# ST_LINK_V2.net
KiCad netlist of a schematic drawn in Altium Designer
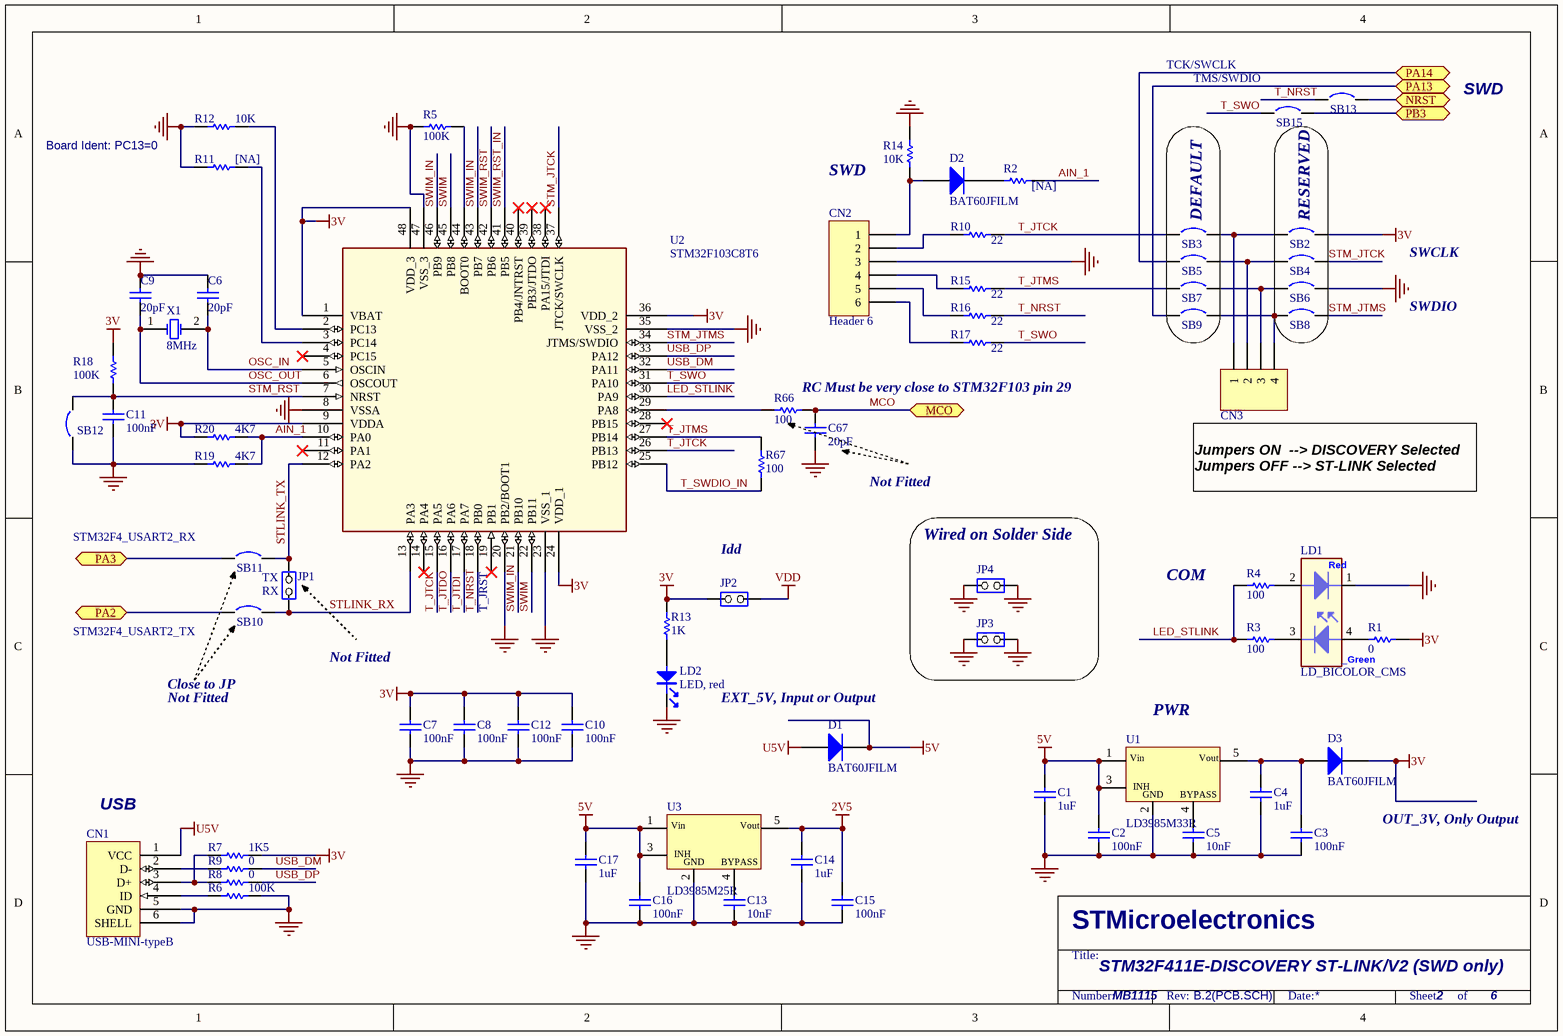
[diagram p0: ST_LINK_V2.SCHDOC]

(export (version "E")
  (design (tool "Eeschema 10.0.6"))
  (components
    (comp (ref "C1")
      (value "1uF")
      (footprint "0603C")
      (description "Capacitor,1uF,16V,X5R,10%,0603,YAGEO")
      (libsource (lib "MCD_TOOLS") (part "Cap_1uF_X5R_10%_0603"))
    )
    (comp (ref "C2")
      (value "100nF")
      (footprint "0402C")
      (description "Capacitor,100nF,16V,X7R,10%,0402,YAGEO")
      (libsource (lib "MCD_TOOLS") (part "Cap_100nF_X7R_10%_0402"))
    )
    (comp (ref "C3")
      (value "100nF")
      (footprint "0402C")
      (description "Capacitor,100nF,16V,X7R,10%,0402,YAGEO")
      (libsource (lib "MCD_TOOLS") (part "Cap_100nF_X7R_10%_0402"))
    )
    (comp (ref "C4")
      (value "1uF")
      (footprint "0603C")
      (description "Capacitor,1uF,16V,X5R,10%,0603,YAGEO")
      (libsource (lib "MCD_TOOLS") (part "Cap_1uF_X5R_10%_0603"))
    )
    (comp (ref "C5")
      (value "10nF")
      (footprint "0603C")
      (description "Capacitor,10nF,50V,X7R,10%,0603,YAGEO")
      (libsource (lib "MCD_TOOLS") (part "Cap_10nF_X7R_10%_0603"))
    )
    (comp (ref "C6")
      (value "20pF")
      (footprint "0402C")
      (description "Capacitor,20pF,50V,NPO,5%,0402,YAGEO")
      (libsource (lib "MCD_TOOLS") (part "Cap_20pF_NPO_5%_0402"))
    )
    (comp (ref "C7")
      (value "100nF")
      (footprint "0402C")
      (description "Capacitor,100nF,16V,X7R,10%,0402,YAGEO")
      (libsource (lib "MCD_TOOLS") (part "Cap_100nF_X7R_10%_0402"))
    )
    (comp (ref "C8")
      (value "100nF")
      (footprint "0402C")
      (description "Capacitor,100nF,16V,X7R,10%,0402,YAGEO")
      (libsource (lib "MCD_TOOLS") (part "Cap_100nF_X7R_10%_0402"))
    )
    (comp (ref "C9")
      (value "20pF")
      (footprint "0402C")
      (description "Capacitor,20pF,50V,NPO,5%,0402,YAGEO")
      (libsource (lib "MCD_TOOLS") (part "Cap_20pF_NPO_5%_0402"))
    )
    (comp (ref "C10")
      (value "100nF")
      (footprint "0402C")
      (description "Capacitor,100nF,16V,X7R,10%,0402,YAGEO")
      (libsource (lib "MCD_TOOLS") (part "Cap_100nF_X7R_10%_0402"))
    )
    (comp (ref "C11")
      (value "100nF")
      (footprint "0402C")
      (description "Capacitor,100nF,16V,X7R,10%,0402,YAGEO")
      (libsource (lib "MCD_TOOLS") (part "Cap_100nF_X7R_10%_0402"))
    )
    (comp (ref "C12")
      (value "100nF")
      (footprint "0402C")
      (description "Capacitor,100nF,16V,X7R,10%,0402,YAGEO")
      (libsource (lib "MCD_TOOLS") (part "Cap_100nF_X7R_10%_0402"))
    )
    (comp (ref "C13")
      (value "10nF")
      (footprint "0603C")
      (description "Capacitor,10nF,50V,X7R,10%,0603,YAGEO")
      (libsource (lib "MCD_TOOLS") (part "Cap_10nF_X7R_10%_0603"))
    )
    (comp (ref "C14")
      (value "1uF")
      (footprint "0603C")
      (description "Capacitor,1uF,16V,X5R,10%,0603,YAGEO")
      (libsource (lib "MCD_TOOLS") (part "Cap_1uF_X5R_10%_0603"))
    )
    (comp (ref "C15")
      (value "100nF")
      (footprint "0402C")
      (description "Capacitor,100nF,16V,X7R,10%,0402,YAGEO")
      (libsource (lib "MCD_TOOLS") (part "Cap_100nF_X7R_10%_0402"))
    )
    (comp (ref "C16")
      (value "100nF")
      (footprint "0402C")
      (description "Capacitor,100nF,16V,X7R,10%,0402,YAGEO")
      (libsource (lib "MCD_TOOLS") (part "Cap_100nF_X7R_10%_0402"))
    )
    (comp (ref "C17")
      (value "1uF")
      (footprint "0603C")
      (description "Capacitor,1uF,16V,X5R,10%,0603,YAGEO")
      (libsource (lib "MCD_TOOLS") (part "Cap_1uF_X5R_10%_0603"))
    )
    (comp (ref "C67")
      (value "20pF")
      (footprint "0402C")
      (description "Capacitor,20pF,50V,NPO,5%,0402,YAGEO")
      (libsource (lib "MCD_TOOLS") (part "Cap_20pF_NPO_5%_0402"))
    )
    (comp (ref "CN1")
      (value "USB-MINI-typeB")
      (footprint "STM-SMEE:USB-MINI-B-SMD")
      (description "USB,MINI-USB-5P/F, 5075BMR-05-M")
      (libsource (lib "MCD_TOOLS") (part "USB-MINI-typeB connector"))
    )
    (comp (ref "CN2")
      (value "Header 6")
      (footprint "HDR1X6")
      (description "Header, 6-Pin")
      (fields (field (name "PUBLISHER") "Altium Limited"))
      (libsource (lib "Miscellaneous Connectors") (part "Header 6"))
    )
    (comp (ref "CN3")
      (value "Header 4")
      (footprint "Header 4")
      (description "Header, 4-Pin")
      (fields (field (name "PUBLISHER") "Altium Limited"))
      (libsource (lib "MB963_1") (part "Header 4"))
    )
    (comp (ref "D1")
      (value "BAT60JFILM")
      (footprint "STM-SMEE:SOD323/A")
      (libsource (lib "MCD_TOOLS") (part "BAT60JFILM"))
    )
    (comp (ref "D2")
      (value "BAT60JFILM")
      (footprint "STM-SMEE:SOD323/A")
      (libsource (lib "MCD_TOOLS") (part "BAT60JFILM"))
    )
    (comp (ref "D3")
      (value "BAT60JFILM")
      (footprint "STM-SMEE:SOD323/A")
      (libsource (lib "MCD_TOOLS") (part "BAT60JFILM"))
    )
    (comp (ref "JP1") (value "JP2") (footprint "SIP2/2.54") (libsource (lib "MCD_TOOLS") (part "JP2")))
    (comp (ref "JP2") (value "~") (footprint "SIP2/2.54") (libsource (lib "*") (part "JP2")))
    (comp (ref "JP3") (value "~") (footprint "SIP2/2.54") (libsource (lib "*") (part "JP2")))
    (comp (ref "JP4") (value "~") (footprint "SIP2/2.54") (libsource (lib "*") (part "JP2")))
    (comp (ref "LD1")
      (value "LD_BICOLOR_CMS")
      (footprint "STM-SMEE:HSMF-A201")
      (description "Bicolor Led")
      (libsource (lib "MCD_TOOLS") (part "LD_BICOLOR_CMS"))
    )
    (comp (ref "LD2")
      (value "LED, red")
      (footprint "0603D")
      (description "LED,red,0603,19-213-R6C-AP1Q2B/3T,everlight")
      (libsource (lib "MCD_TOOLS") (part "LED_red"))
    )
    (comp (ref "R1")
      (value "0")
      (footprint "STM-SMEE:0402R")
      (description "Resistor,0,0402")
      (libsource (lib "MCD_TOOLS") (part "Res_0_0402"))
    )
    (comp (ref "R2")
      (value "[NA]")
      (footprint "STM-SMEE:0402R")
      (description "Resistor,[NA],0402")
      (libsource (lib "MCD_TOOLS") (part "Res_NA_0402"))
    )
    (comp (ref "R3")
      (value "100")
      (footprint "0402R")
      (description "Resistor")
      (fields (field (name "PUBLISHER") "Altium Limited"))
      (libsource (lib "MB915_1") (part "res1"))
    )
    (comp (ref "R4")
      (value "100")
      (footprint "0402R")
      (description "Resistor")
      (fields (field (name "PUBLISHER") "Altium Limited"))
      (libsource (lib "MB915_1") (part "res1"))
    )
    (comp (ref "R5")
      (value "100K")
      (footprint "0402R")
      (description "Resistor")
      (fields (field (name "PUBLISHER") "Altium Limited"))
      (libsource (lib "MB915_1") (part "res1"))
    )
    (comp (ref "R6")
      (value "100K")
      (footprint "0402R")
      (description "Resistor")
      (fields (field (name "PUBLISHER") "Altium Limited"))
      (libsource (lib "MB915_1") (part "res1"))
    )
    (comp (ref "R7")
      (value "1K5")
      (footprint "0402R")
      (description "Resistor")
      (fields (field (name "PUBLISHER") "Altium Limited"))
      (libsource (lib "MB915_1") (part "res1"))
    )
    (comp (ref "R8")
      (value "0")
      (footprint "STM-SMEE:0402R")
      (description "Resistor,0,0402")
      (libsource (lib "MCD_TOOLS") (part "Res_0_0402"))
    )
    (comp (ref "R9")
      (value "0")
      (footprint "STM-SMEE:0402R")
      (description "Resistor,0,0402")
      (libsource (lib "MCD_TOOLS") (part "Res_0_0402"))
    )
    (comp (ref "R10")
      (value "22")
      (footprint "0402R")
      (description "Resistor")
      (fields (field (name "PUBLISHER") "Altium Limited"))
      (libsource (lib "MB915_1") (part "res1"))
    )
    (comp (ref "R11")
      (value "[NA]")
      (footprint "STM-SMEE:0402R")
      (description "Resistor,[NA],0402")
      (libsource (lib "MCD_TOOLS") (part "Res_NA_0402"))
    )
    (comp (ref "R12")
      (value "10K")
      (footprint "0402R")
      (description "Resistor")
      (fields (field (name "PUBLISHER") "Altium Limited"))
      (libsource (lib "MB915_1") (part "res1"))
    )
    (comp (ref "R13")
      (value "1K")
      (footprint "0402R")
      (description "Resistor")
      (fields (field (name "PUBLISHER") "Altium Limited"))
      (libsource (lib "MB915_1") (part "res1"))
    )
    (comp (ref "R14")
      (value "10K")
      (footprint "0402R")
      (description "Resistor")
      (fields (field (name "PUBLISHER") "Altium Limited"))
      (libsource (lib "MB915_1") (part "res1"))
    )
    (comp (ref "R15")
      (value "22")
      (footprint "0402R")
      (description "Resistor")
      (fields (field (name "PUBLISHER") "Altium Limited"))
      (libsource (lib "MB915_1") (part "res1"))
    )
    (comp (ref "R16")
      (value "22")
      (footprint "0402R")
      (description "Resistor")
      (fields (field (name "PUBLISHER") "Altium Limited"))
      (libsource (lib "MB915_1") (part "res1"))
    )
    (comp (ref "R17")
      (value "22")
      (footprint "0402R")
      (description "Resistor")
      (fields (field (name "PUBLISHER") "Altium Limited"))
      (libsource (lib "MB915_1") (part "res1"))
    )
    (comp (ref "R18")
      (value "100K")
      (footprint "0402R")
      (description "Resistor")
      (fields (field (name "PUBLISHER") "Altium Limited"))
      (libsource (lib "MB915_1") (part "res1"))
    )
    (comp (ref "R19")
      (value "4K7")
      (footprint "0402R")
      (description "Resistor")
      (fields (field (name "PUBLISHER") "Altium Limited"))
      (libsource (lib "MB915_1") (part "res1"))
    )
    (comp (ref "R20")
      (value "4K7")
      (footprint "0402R")
      (description "Resistor")
      (fields (field (name "PUBLISHER") "Altium Limited"))
      (libsource (lib "MB915_1") (part "res1"))
    )
    (comp (ref "R66")
      (value "100")
      (footprint "0402R")
      (description "Resistor")
      (fields (field (name "PUBLISHER") "Altium Limited"))
      (libsource (lib "MB915_1") (part "res1"))
    )
    (comp (ref "R67")
      (value "100")
      (footprint "0402R")
      (description "Resistor")
      (fields (field (name "PUBLISHER") "Altium Limited"))
      (libsource (lib "MB915_1") (part "res1"))
    )
    (comp (ref "SB2")
      (value "Circuit Breaker")
      (footprint "JP2_SMD")
      (libsource (lib "MCD_TOOLS") (part "Circuit Breaker"))
    )
    (comp (ref "SB3")
      (value "Circuit Breaker")
      (footprint "JP2_SMD")
      (libsource (lib "MCD_TOOLS") (part "Circuit Breaker"))
    )
    (comp (ref "SB4")
      (value "Circuit Breaker")
      (footprint "JP2_SMD")
      (libsource (lib "MCD_TOOLS") (part "Circuit Breaker"))
    )
    (comp (ref "SB5")
      (value "Circuit Breaker")
      (footprint "JP2_SMD")
      (libsource (lib "MCD_TOOLS") (part "Circuit Breaker"))
    )
    (comp (ref "SB6")
      (value "Circuit Breaker")
      (footprint "JP2_SMD")
      (libsource (lib "MCD_TOOLS") (part "Circuit Breaker"))
    )
    (comp (ref "SB7")
      (value "Circuit Breaker")
      (footprint "JP2_SMD")
      (libsource (lib "MCD_TOOLS") (part "Circuit Breaker"))
    )
    (comp (ref "SB8")
      (value "Circuit Breaker")
      (footprint "JP2_SMD")
      (libsource (lib "MCD_TOOLS") (part "Circuit Breaker"))
    )
    (comp (ref "SB9")
      (value "Circuit Breaker")
      (footprint "JP2_SMD")
      (libsource (lib "MCD_TOOLS") (part "Circuit Breaker"))
    )
    (comp (ref "SB10")
      (value "Circuit Breaker")
      (footprint "JP2_SMD")
      (libsource (lib "MCD_TOOLS") (part "Circuit Breaker"))
    )
    (comp (ref "SB11")
      (value "Circuit Breaker")
      (footprint "JP2_SMD")
      (libsource (lib "MCD_TOOLS") (part "Circuit Breaker"))
    )
    (comp (ref "SB12")
      (value "Circuit Breaker")
      (footprint "JP2_SMD")
      (libsource (lib "MCD_TOOLS") (part "Circuit Breaker"))
    )
    (comp (ref "SB13")
      (value "Circuit Breaker")
      (footprint "JP2_SMD")
      (libsource (lib "MCD_TOOLS") (part "Circuit Breaker"))
    )
    (comp (ref "SB15")
      (value "Circuit Breaker")
      (footprint "JP2_SMD")
      (libsource (lib "MCD_TOOLS") (part "Circuit Breaker"))
    )
    (comp (ref "U1")
      (value "LD3985M33R")
      (footprint "STM-SMEE:SOT-23-5L")
      (description "Ultra low drop-low noise BiCMOS voltage, regulators low ESR capacitors compatible")
      (libsource (lib "MCD_TOOLS") (part "LD3985M33R"))
    )
    (comp (ref "U2")
      (value "STM32F103C8T6")
      (footprint "STM-SMEE:QFP48 7X7")
      (description "Medium-density performance line ARM-based 32-bit MCU with 64KB Flash")
      (libsource (lib "MCD_TOOLS") (part "STM32F103C8T6"))
    )
    (comp (ref "U3")
      (value "LD3985M25R")
      (footprint "STM-SMEE:SOT-23-5L")
      (description "Ultra low drop-low noise BiCMOS voltage, regulators low ESR capacitors compatible")
      (libsource (lib "MCD_TOOLS") (part "LD3985M25R"))
    )
    (comp (ref "X1")
      (value "8MHz")
      (footprint "STM-SMEE:XTAL1")
      (description "Crystal Oscillator,8Mhz,20PF,20PPM,-10-70 degree,DIP,HC-49S")
      (libsource (lib "MCD_TOOLS") (part "XTAL_8MHZ_20PPM"))
    )
  )
  (nets
    (net (code "1") (name "/AIN_1") (class "Default")
      (node (ref "R19") (pin "2") (pinfunction "2_2") (pintype "passive"))
      (node (ref "R2") (pin "2") (pinfunction "2_2") (pintype "passive"))
      (node (ref "R20") (pin "2") (pinfunction "2_2") (pintype "passive"))
      (node (ref "U2") (pin "10") (pinfunction "PA0_10") (pintype "bidirectional"))
    )
    (net (code "2") (name "/LED_STLINK") (class "Default")
      (node (ref "R3") (pin "1") (pinfunction "1_1") (pintype "passive"))
      (node (ref "R4") (pin "1") (pinfunction "1_1") (pintype "passive"))
      (node (ref "U2") (pin "30") (pinfunction "PA9_30") (pintype "bidirectional"))
    )
    (net (code "3") (name "/MCO") (class "Default")
      (node (ref "C67") (pin "1") (pinfunction "1_1") (pintype "passive"))
      (node (ref "R66") (pin "2") (pinfunction "2_2") (pintype "passive"))
    )
    (net (code "4") (name "/NRST") (class "Default")
      (node (ref "SB13") (pin "2") (pinfunction "2_2") (pintype "passive"))
    )
    (net (code "5") (name "/OSC_IN") (class "Default")
      (node (ref "C6") (pin "2") (pinfunction "2_2") (pintype "passive"))
      (node (ref "U2") (pin "5") (pinfunction "OSCIN_5") (pintype "input"))
      (node (ref "X1") (pin "2") (pinfunction "OSC2_2") (pintype "passive"))
    )
    (net (code "6") (name "/OSC_OUT") (class "Default")
      (node (ref "C9") (pin "2") (pinfunction "2_2") (pintype "passive"))
      (node (ref "U2") (pin "6") (pinfunction "OSCOUT_6") (pintype "output"))
      (node (ref "X1") (pin "1") (pinfunction "OSC1_1") (pintype "passive"))
    )
    (net (code "7") (name "/PA2") (class "Default")
      (node (ref "SB10") (pin "1") (pinfunction "1_1") (pintype "passive"))
    )
    (net (code "8") (name "/PA3") (class "Default")
      (node (ref "SB11") (pin "1") (pinfunction "1_1") (pintype "passive"))
    )
    (net (code "9") (name "/PA13") (class "Default")
      (node (ref "SB9") (pin "1") (pinfunction "1_1") (pintype "passive"))
    )
    (net (code "10") (name "/PA14") (class "Default")
      (node (ref "SB5") (pin "1") (pinfunction "1_1") (pintype "passive"))
    )
    (net (code "11") (name "/PB3") (class "Default")
      (node (ref "SB15") (pin "2") (pinfunction "2_2") (pintype "passive"))
    )
    (net (code "12") (name "/STLINK_RX") (class "Default")
      (node (ref "JP1") (pin "1") (pinfunction "COMMON_1") (pintype "passive"))
      (node (ref "SB10") (pin "2") (pinfunction "2_2") (pintype "passive"))
      (node (ref "U2") (pin "13") (pinfunction "PA3_13") (pintype "bidirectional"))
    )
    (net (code "13") (name "/STLINK_TX") (class "Default")
      (node (ref "JP1") (pin "2") (pinfunction "NO_2") (pintype "passive"))
      (node (ref "SB11") (pin "2") (pinfunction "2_2") (pintype "passive"))
      (node (ref "U2") (pin "12") (pinfunction "PA2_12") (pintype "bidirectional"))
    )
    (net (code "14") (name "/STM_JTCK") (class "Default")
      (node (ref "SB4") (pin "2") (pinfunction "2_2") (pintype "passive"))
      (node (ref "U2") (pin "37") (pinfunction "JTCK/SWCLK_37") (pintype "bidirectional"))
    )
    (net (code "15") (name "/STM_JTMS") (class "Default")
      (node (ref "SB8") (pin "2") (pinfunction "2_2") (pintype "passive"))
      (node (ref "U2") (pin "34") (pinfunction "JTMS/SWDIO_34") (pintype "bidirectional"))
    )
    (net (code "16") (name "/STM_RST") (class "Default")
      (node (ref "C11") (pin "2") (pinfunction "2_2") (pintype "passive"))
      (node (ref "R18") (pin "1") (pinfunction "1_1") (pintype "passive"))
      (node (ref "SB12") (pin "2") (pinfunction "2_2") (pintype "passive"))
      (node (ref "U2") (pin "7") (pinfunction "NRST_7") (pintype "input"))
    )
    (net (code "17") (name "/SWIM") (class "Default")
      (node (ref "U2") (pin "22") (pinfunction "PB11_22") (pintype "bidirectional"))
      (node (ref "U2") (pin "45") (pinfunction "PB8_45") (pintype "bidirectional"))
    )
    (net (code "18") (name "/SWIM_IN") (class "Default")
      (node (ref "U2") (pin "21") (pinfunction "PB10_21") (pintype "bidirectional"))
      (node (ref "U2") (pin "43") (pinfunction "PB7_43") (pintype "bidirectional"))
      (node (ref "U2") (pin "46") (pinfunction "PB9_46") (pintype "bidirectional"))
    )
    (net (code "19") (name "/SWIM_RST") (class "Default")
      (node (ref "U2") (pin "42") (pinfunction "PB6_42") (pintype "bidirectional"))
    )
    (net (code "20") (name "/SWIM_RST_IN") (class "Default")
      (node (ref "U2") (pin "41") (pinfunction "PB5_41") (pintype "bidirectional"))
    )
    (net (code "21") (name "/T_JTCK") (class "Default")
      (node (ref "R10") (pin "2") (pinfunction "2_2") (pintype "passive"))
      (node (ref "SB3") (pin "1") (pinfunction "1_1") (pintype "passive"))
      (node (ref "U2") (pin "15") (pinfunction "PA5_15") (pintype "bidirectional"))
      (node (ref "U2") (pin "26") (pinfunction "PB13_26") (pintype "bidirectional"))
    )
    (net (code "22") (name "/T_JTDI") (class "Default")
      (node (ref "U2") (pin "17") (pinfunction "PA7_17") (pintype "bidirectional"))
    )
    (net (code "23") (name "/T_JTDO") (class "Default")
      (node (ref "U2") (pin "16") (pinfunction "PA6_16") (pintype "bidirectional"))
    )
    (net (code "24") (name "/T_JTMS") (class "Default")
      (node (ref "R15") (pin "2") (pinfunction "2_2") (pintype "passive"))
      (node (ref "R67") (pin "2") (pinfunction "2_2") (pintype "passive"))
      (node (ref "SB7") (pin "1") (pinfunction "1_1") (pintype "passive"))
      (node (ref "U2") (pin "27") (pinfunction "PB14_27") (pintype "bidirectional"))
    )
    (net (code "25") (name "/T_NRST") (class "Default")
      (node (ref "R16") (pin "2") (pinfunction "2_2") (pintype "passive"))
      (node (ref "SB13") (pin "1") (pinfunction "1_1") (pintype "passive"))
      (node (ref "U2") (pin "18") (pinfunction "PB0_18") (pintype "bidirectional"))
    )
    (net (code "26") (name "/T_SWDIO_IN") (class "Default")
      (node (ref "R67") (pin "1") (pinfunction "1_1") (pintype "passive"))
      (node (ref "U2") (pin "25") (pinfunction "PB12_25") (pintype "bidirectional"))
    )
    (net (code "27") (name "/T_SWO") (class "Default")
      (node (ref "R17") (pin "2") (pinfunction "2_2") (pintype "passive"))
      (node (ref "SB15") (pin "1") (pinfunction "1_1") (pintype "passive"))
      (node (ref "U2") (pin "31") (pinfunction "PA10_31") (pintype "bidirectional"))
    )
    (net (code "28") (name "/USB_DM") (class "Default")
      (node (ref "R9") (pin "2") (pinfunction "2_2") (pintype "passive"))
      (node (ref "U2") (pin "32") (pinfunction "PA11_32") (pintype "bidirectional"))
    )
    (net (code "29") (name "/USB_DP") (class "Default")
      (node (ref "R8") (pin "2") (pinfunction "2_2") (pintype "passive"))
      (node (ref "U2") (pin "33") (pinfunction "PA12_33") (pintype "bidirectional"))
    )
    (net (code "30") (name "2V5") (class "Default")
      (node (ref "C14") (pin "1") (pinfunction "1_1") (pintype "passive"))
      (node (ref "C15") (pin "2") (pinfunction "2_2") (pintype "passive"))
      (node (ref "U3") (pin "5") (pinfunction "Vout_5") (pintype "passive"))
    )
    (net (code "31") (name "3V") (class "Default")
      (node (ref "C10") (pin "2") (pinfunction "2_2") (pintype "passive"))
      (node (ref "C12") (pin "1") (pinfunction "1_1") (pintype "passive"))
      (node (ref "C7") (pin "2") (pinfunction "2_2") (pintype "passive"))
      (node (ref "C8") (pin "2") (pinfunction "2_2") (pintype "passive"))
      (node (ref "D3") (pin "2") (pinfunction "K_2") (pintype "passive"))
      (node (ref "JP2") (pin "1") (pinfunction "COMMON_1") (pintype "passive"))
      (node (ref "R1") (pin "2") (pinfunction "2_2") (pintype "passive"))
      (node (ref "R13") (pin "2") (pinfunction "2_2") (pintype "passive"))
      (node (ref "R18") (pin "2") (pinfunction "2_2") (pintype "passive"))
      (node (ref "R20") (pin "1") (pinfunction "1_1") (pintype "passive"))
      (node (ref "R7") (pin "2") (pinfunction "2_2") (pintype "passive"))
      (node (ref "SB2") (pin "2") (pinfunction "2_2") (pintype "passive"))
      (node (ref "U2") (pin "1") (pinfunction "VBAT_1") (pintype "power_in"))
      (node (ref "U2") (pin "24") (pinfunction "VDD_1_24") (pintype "power_in"))
      (node (ref "U2") (pin "36") (pinfunction "VDD_2_36") (pintype "power_in"))
      (node (ref "U2") (pin "48") (pinfunction "VDD_3_48") (pintype "power_in"))
      (node (ref "U2") (pin "9") (pinfunction "VDDA_9") (pintype "power_in"))
    )
    (net (code "32") (name "5V") (class "Default")
      (node (ref "C1") (pin "2") (pinfunction "2_2") (pintype "passive"))
      (node (ref "C16") (pin "2") (pinfunction "2_2") (pintype "passive"))
      (node (ref "C17") (pin "2") (pinfunction "2_2") (pintype "passive"))
      (node (ref "C2") (pin "2") (pinfunction "2_2") (pintype "passive"))
      (node (ref "D1") (pin "2") (pinfunction "K_2") (pintype "passive"))
      (node (ref "U1") (pin "1") (pinfunction "Vin_1") (pintype "passive"))
      (node (ref "U1") (pin "3") (pinfunction "CE_3") (pintype "passive"))
      (node (ref "U3") (pin "1") (pinfunction "Vin_1") (pintype "passive"))
      (node (ref "U3") (pin "3") (pinfunction "CE_3") (pintype "passive"))
    )
    (net (code "33") (name "GND") (class "Default")
      (node (ref "C1") (pin "1") (pinfunction "1_1") (pintype "passive"))
      (node (ref "C10") (pin "1") (pinfunction "1_1") (pintype "passive"))
      (node (ref "C11") (pin "1") (pinfunction "1_1") (pintype "passive"))
      (node (ref "C12") (pin "2") (pinfunction "2_2") (pintype "passive"))
      (node (ref "C13") (pin "1") (pinfunction "1_1") (pintype "passive"))
      (node (ref "C14") (pin "2") (pinfunction "2_2") (pintype "passive"))
      (node (ref "C15") (pin "1") (pinfunction "1_1") (pintype "passive"))
      (node (ref "C16") (pin "1") (pinfunction "1_1") (pintype "passive"))
      (node (ref "C17") (pin "1") (pinfunction "1_1") (pintype "passive"))
      (node (ref "C2") (pin "1") (pinfunction "1_1") (pintype "passive"))
      (node (ref "C3") (pin "1") (pinfunction "1_1") (pintype "passive"))
      (node (ref "C4") (pin "2") (pinfunction "2_2") (pintype "passive"))
      (node (ref "C5") (pin "1") (pinfunction "1_1") (pintype "passive"))
      (node (ref "C6") (pin "1") (pinfunction "1_1") (pintype "passive"))
      (node (ref "C67") (pin "2") (pinfunction "2_2") (pintype "passive"))
      (node (ref "C7") (pin "1") (pinfunction "1_1") (pintype "passive"))
      (node (ref "C8") (pin "1") (pinfunction "1_1") (pintype "passive"))
      (node (ref "C9") (pin "1") (pinfunction "1_1") (pintype "passive"))
      (node (ref "CN1") (pin "5") (pinfunction "GND_5") (pintype "passive"))
      (node (ref "CN1") (pin "6") (pinfunction "SHELL_6") (pintype "passive"))
      (node (ref "CN2") (pin "3") (pinfunction "3_3") (pintype "passive"))
      (node (ref "JP3") (pin "1") (pinfunction "COMMON_1") (pintype "passive"))
      (node (ref "JP3") (pin "2") (pinfunction "NO_2") (pintype "passive"))
      (node (ref "JP4") (pin "1") (pinfunction "COMMON_1") (pintype "passive"))
      (node (ref "JP4") (pin "2") (pinfunction "NO_2") (pintype "passive"))
      (node (ref "LD1") (pin "1") (pinfunction "1_1") (pintype "passive"))
      (node (ref "LD2") (pin "2") (pintype "passive"))
      (node (ref "R11") (pin "1") (pinfunction "1_1") (pintype "passive"))
      (node (ref "R12") (pin "1") (pinfunction "1_1") (pintype "passive"))
      (node (ref "R14") (pin "2") (pinfunction "2_2") (pintype "passive"))
      (node (ref "R19") (pin "1") (pinfunction "1_1") (pintype "passive"))
      (node (ref "R5") (pin "1") (pinfunction "1_1") (pintype "passive"))
      (node (ref "R6") (pin "2") (pinfunction "2_2") (pintype "passive"))
      (node (ref "SB12") (pin "1") (pinfunction "1_1") (pintype "passive"))
      (node (ref "SB6") (pin "2") (pinfunction "2_2") (pintype "passive"))
      (node (ref "U1") (pin "2") (pinfunction "GND_2") (pintype "passive"))
      (node (ref "U2") (pin "20") (pinfunction "PB2/BOOT1_20") (pintype "bidirectional"))
      (node (ref "U2") (pin "23") (pinfunction "VSS_1_23") (pintype "power_in"))
      (node (ref "U2") (pin "35") (pinfunction "VSS_2_35") (pintype "power_in"))
      (node (ref "U2") (pin "47") (pinfunction "VSS_3_47") (pintype "power_in"))
      (node (ref "U2") (pin "8") (pinfunction "VSSA_8") (pintype "power_in"))
      (node (ref "U3") (pin "2") (pinfunction "GND_2") (pintype "passive"))
    )
    (net (code "34") (name "Net-(CN1-D+)") (class "Default")
      (node (ref "CN1") (pin "3") (pinfunction "D+_3") (pintype "bidirectional"))
      (node (ref "R7") (pin "1") (pinfunction "1_1") (pintype "passive"))
      (node (ref "R8") (pin "1") (pinfunction "1_1") (pintype "passive"))
    )
    (net (code "35") (name "Net-(CN1-D-)") (class "Default")
      (node (ref "CN1") (pin "2") (pinfunction "D-_2") (pintype "bidirectional"))
      (node (ref "R9") (pin "1") (pinfunction "1_1") (pintype "passive"))
    )
    (net (code "36") (name "Net-(CN1-ID)") (class "Default")
      (node (ref "CN1") (pin "4") (pinfunction "ID_4") (pintype "input"))
      (node (ref "R6") (pin "1") (pinfunction "1_1") (pintype "passive"))
    )
    (net (code "37") (name "Net-(CN2-Pad2)") (class "Default")
      (node (ref "CN2") (pin "2") (pinfunction "2_2") (pintype "passive"))
      (node (ref "R10") (pin "1") (pinfunction "1_1") (pintype "passive"))
    )
    (net (code "38") (name "Net-(CN2-Pad4)") (class "Default")
      (node (ref "CN2") (pin "4") (pinfunction "4_4") (pintype "passive"))
      (node (ref "R15") (pin "1") (pinfunction "1_1") (pintype "passive"))
    )
    (net (code "39") (name "Net-(CN2-Pad5)") (class "Default")
      (node (ref "CN2") (pin "5") (pinfunction "5_5") (pintype "passive"))
      (node (ref "R16") (pin "1") (pinfunction "1_1") (pintype "passive"))
    )
    (net (code "40") (name "Net-(CN2-Pad6)") (class "Default")
      (node (ref "CN2") (pin "6") (pinfunction "6_6") (pintype "passive"))
      (node (ref "R17") (pin "1") (pinfunction "1_1") (pintype "passive"))
    )
    (net (code "41") (name "Net-(CN3-Pad1)") (class "Default")
      (node (ref "CN3") (pin "1") (pinfunction "1_1") (pintype "passive"))
      (node (ref "SB2") (pin "1") (pinfunction "1_1") (pintype "passive"))
      (node (ref "SB3") (pin "2") (pinfunction "2_2") (pintype "passive"))
    )
    (net (code "42") (name "Net-(CN3-Pad2)") (class "Default")
      (node (ref "CN3") (pin "2") (pinfunction "2_2") (pintype "passive"))
      (node (ref "SB4") (pin "1") (pinfunction "1_1") (pintype "passive"))
      (node (ref "SB5") (pin "2") (pinfunction "2_2") (pintype "passive"))
    )
    (net (code "43") (name "Net-(CN3-Pad3)") (class "Default")
      (node (ref "CN3") (pin "3") (pinfunction "3_3") (pintype "passive"))
      (node (ref "SB6") (pin "1") (pinfunction "1_1") (pintype "passive"))
      (node (ref "SB7") (pin "2") (pinfunction "2_2") (pintype "passive"))
    )
    (net (code "44") (name "Net-(CN3-Pad4)") (class "Default")
      (node (ref "CN3") (pin "4") (pinfunction "4_4") (pintype "passive"))
      (node (ref "SB8") (pin "1") (pinfunction "1_1") (pintype "passive"))
      (node (ref "SB9") (pin "2") (pinfunction "2_2") (pintype "passive"))
    )
    (net (code "45") (name "Net-(D2-A)") (class "Default")
      (node (ref "CN2") (pin "1") (pinfunction "1_1") (pintype "passive"))
      (node (ref "D2") (pin "1") (pinfunction "A_1") (pintype "passive"))
      (node (ref "R14") (pin "1") (pinfunction "1_1") (pintype "passive"))
    )
    (net (code "46") (name "Net-(D2-K)") (class "Default")
      (node (ref "D2") (pin "2") (pinfunction "K_2") (pintype "passive"))
      (node (ref "R2") (pin "1") (pinfunction "1_1") (pintype "passive"))
    )
    (net (code "47") (name "Net-(D3-A)") (class "Default")
      (node (ref "C3") (pin "2") (pinfunction "2_2") (pintype "passive"))
      (node (ref "C4") (pin "1") (pinfunction "1_1") (pintype "passive"))
      (node (ref "D3") (pin "1") (pinfunction "A_1") (pintype "passive"))
      (node (ref "U1") (pin "5") (pinfunction "Vout_5") (pintype "passive"))
    )
    (net (code "48") (name "Net-(LD1-Pad2)") (class "Default")
      (node (ref "LD1") (pin "2") (pinfunction "2_2") (pintype "passive"))
      (node (ref "R4") (pin "2") (pinfunction "2_2") (pintype "passive"))
    )
    (net (code "49") (name "Net-(LD1-Pad3)") (class "Default")
      (node (ref "LD1") (pin "3") (pinfunction "3_3") (pintype "passive"))
      (node (ref "R3") (pin "2") (pinfunction "2_2") (pintype "passive"))
    )
    (net (code "50") (name "Net-(LD1-Pad4)") (class "Default")
      (node (ref "LD1") (pin "4") (pinfunction "4_4") (pintype "passive"))
      (node (ref "R1") (pin "1") (pinfunction "1_1") (pintype "passive"))
    )
    (net (code "51") (name "Net-(LD2-Pad1)") (class "Default")
      (node (ref "LD2") (pin "1") (pintype "passive"))
      (node (ref "R13") (pin "1") (pinfunction "1_1") (pintype "passive"))
    )
    (net (code "52") (name "Net-(U1-BYPASS)") (class "Default")
      (node (ref "C5") (pin "2") (pinfunction "2_2") (pintype "passive"))
      (node (ref "U1") (pin "4") (pinfunction "BYPASS_4") (pintype "passive"))
    )
    (net (code "53") (name "Net-(U2-BOOT0)") (class "Default")
      (node (ref "R5") (pin "2") (pinfunction "2_2") (pintype "passive"))
      (node (ref "U2") (pin "44") (pinfunction "BOOT0_44") (pintype "bidirectional"))
    )
    (net (code "54") (name "Net-(U2-PA8)") (class "Default")
      (node (ref "R66") (pin "1") (pinfunction "1_1") (pintype "passive"))
      (node (ref "U2") (pin "29") (pinfunction "PA8_29") (pintype "bidirectional"))
    )
    (net (code "55") (name "Net-(U2-PC13)") (class "Default")
      (node (ref "R12") (pin "2") (pinfunction "2_2") (pintype "passive"))
      (node (ref "U2") (pin "2") (pinfunction "PC13_2") (pintype "bidirectional"))
    )
    (net (code "56") (name "Net-(U2-PC14)") (class "Default")
      (node (ref "R11") (pin "2") (pinfunction "2_2") (pintype "passive"))
      (node (ref "U2") (pin "3") (pinfunction "PC14_3") (pintype "bidirectional"))
    )
    (net (code "57") (name "Net-(U3-BYPASS)") (class "Default")
      (node (ref "C13") (pin "2") (pinfunction "2_2") (pintype "passive"))
      (node (ref "U3") (pin "4") (pinfunction "BYPASS_4") (pintype "passive"))
    )
    (net (code "58") (name "U5V") (class "Default")
      (node (ref "CN1") (pin "1") (pinfunction "VCC_1") (pintype "power_in"))
      (node (ref "D1") (pin "1") (pinfunction "A_1") (pintype "passive"))
    )
    (net (code "59") (name "VDD") (class "Default")
      (node (ref "JP2") (pin "2") (pinfunction "NO_2") (pintype "passive"))
    )
    (net (code "60") (name "unconnected-(U2-PA1-Pad11)") (class "Default")
      (node (ref "U2") (pin "11") (pinfunction "PA1_11") (pintype "bidirectional+no_connect"))
    )
    (net (code "61") (name "unconnected-(U2-PA4-Pad14)") (class "Default")
      (node (ref "U2") (pin "14") (pinfunction "PA4_14") (pintype "bidirectional+no_connect"))
    )
    (net (code "62") (name "unconnected-(U2-PA15{slash}JTDI-Pad38)") (class "Default")
      (node (ref "U2") (pin "38") (pinfunction "PA15/JTDI_38") (pintype "bidirectional+no_connect"))
    )
    (net (code "63") (name "unconnected-(U2-PB1-Pad19)") (class "Default")
      (node (ref "U2") (pin "19") (pinfunction "PB1_19") (pintype "input+no_connect"))
    )
    (net (code "64") (name "unconnected-(U2-PB3{slash}JTDO-Pad39)") (class "Default")
      (node (ref "U2") (pin "39") (pinfunction "PB3/JTDO_39") (pintype "bidirectional+no_connect"))
    )
    (net (code "65") (name "unconnected-(U2-PB4{slash}JNTRST-Pad40)") (class "Default")
      (node (ref "U2") (pin "40") (pinfunction "PB4/JNTRST_40") (pintype "bidirectional+no_connect"))
    )
    (net (code "66") (name "unconnected-(U2-PB15-Pad28)") (class "Default")
      (node (ref "U2") (pin "28") (pinfunction "PB15_28") (pintype "bidirectional+no_connect"))
    )
    (net (code "67") (name "unconnected-(U2-PC15-Pad4)") (class "Default")
      (node (ref "U2") (pin "4") (pinfunction "PC15_4") (pintype "bidirectional+no_connect"))
    )
  )
)
